# Seal.net
KiCad netlist of a schematic drawn in EAGLE
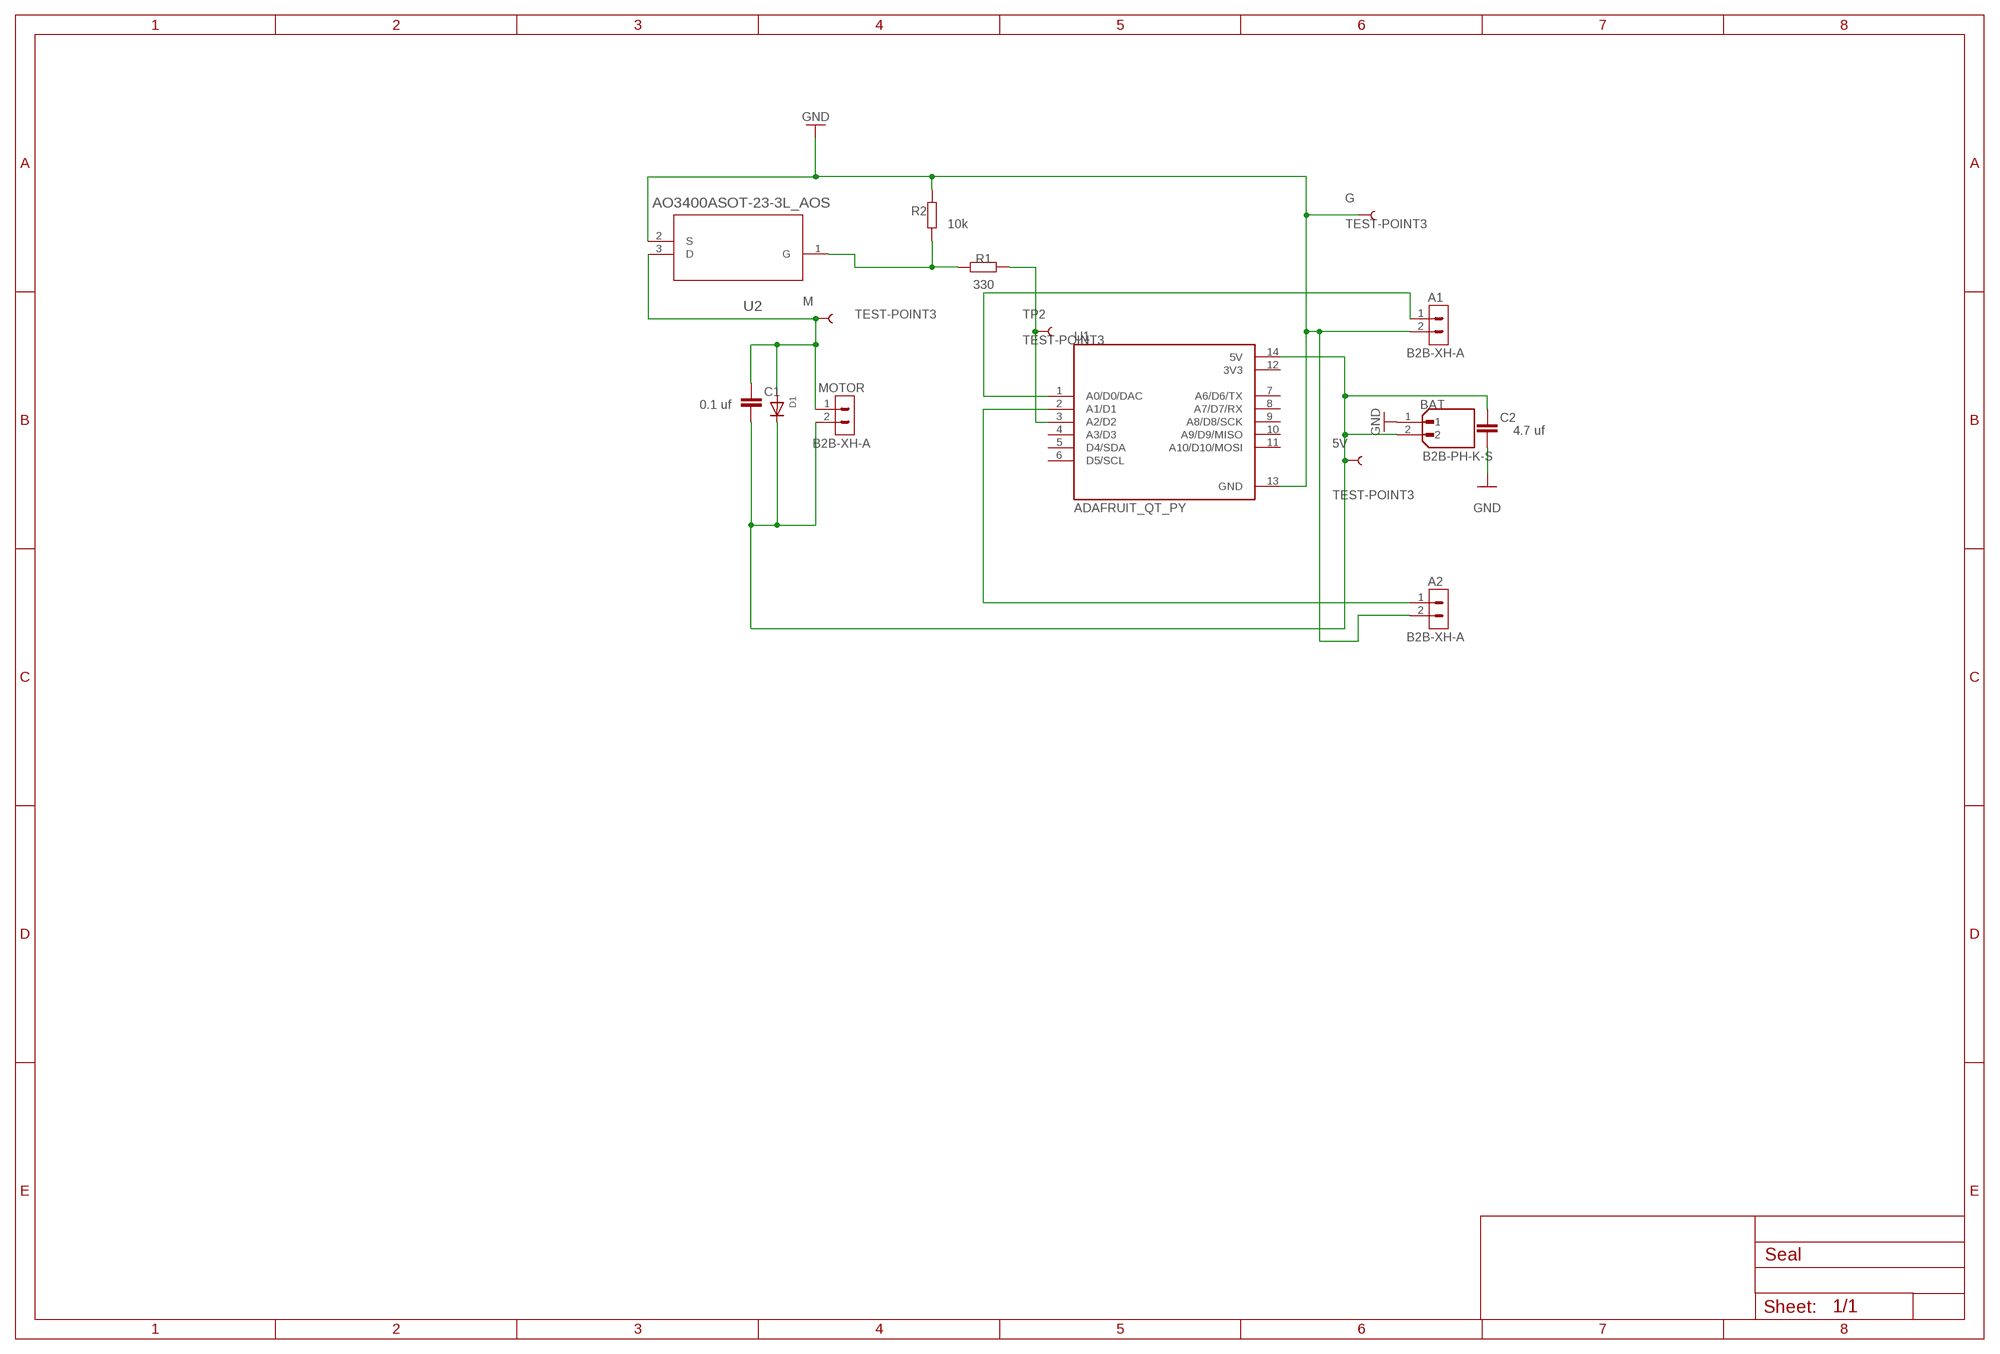
[diagram p0: schematic, sheet 1]

(export (version "E")
  (design (tool "Eeschema 10.0.6"))
  (components
    (comp (ref "5V")
      (value "TEST-POINT3")
      (footprint "eagle-import:PAD.03X.03")
      (libsource (lib "eagle-import") (part "TEST-POINT3"))
    )
    (comp (ref "A1")
      (value "B2B-XH-A")
      (footprint "eagle-import:B2B-XH-A")
      (fields (field (name "MANUFACTURER") "JST Sales America Inc."))
      (libsource (lib "eagle-import") (part "B2B-XH-A"))
    )
    (comp (ref "A2")
      (value "B2B-XH-A")
      (footprint "eagle-import:B2B-XH-A")
      (fields (field (name "MANUFACTURER") "JST Sales America Inc."))
      (libsource (lib "eagle-import") (part "B2B-XH-A"))
    )
    (comp (ref "BAT")
      (value "B2B-PH-K-S")
      (footprint "eagle-import:JST_B2B-PH-K-S")
      (fields (field (name "MF") "JST Sales"))
      (libsource (lib "eagle-import") (part "B2B-PH-K-S"))
    )
    (comp (ref "C1")
      (value "0.1 uf")
      (footprint "eagle-import:CAPC1608X85")
      (libsource (lib "eagle-import") (part "CCHIP-0603(1608-METRIC)_"))
    )
    (comp (ref "C2")
      (value "4.7 uf")
      (footprint "eagle-import:CAPC1608X85")
      (libsource (lib "eagle-import") (part "CCHIP-0603(1608-METRIC)_"))
    )
    (comp (ref "D1")
      (value "DIODESOD-123")
      (footprint "eagle-import:SOD-123")
      (libsource (lib "eagle-import") (part "DIODESOD-123"))
    )
    (comp (ref "G")
      (value "TEST-POINT3")
      (footprint "eagle-import:PAD.03X.03")
      (libsource (lib "eagle-import") (part "TEST-POINT3"))
    )
    (comp (ref "M")
      (value "TEST-POINT3")
      (footprint "eagle-import:PAD.03X.03")
      (libsource (lib "eagle-import") (part "TEST-POINT3"))
    )
    (comp (ref "MOTOR")
      (value "B2B-XH-A")
      (footprint "eagle-import:B2B-XH-A")
      (fields (field (name "MANUFACTURER") "JST Sales America Inc."))
      (libsource (lib "eagle-import") (part "B2B-XH-A"))
    )
    (comp (ref "R1")
      (value "330")
      (footprint "eagle-import:RESC1005X40")
      (libsource (lib "eagle-import") (part "RCHIP-0402(1005-METRIC)_"))
    )
    (comp (ref "R2")
      (value "10k")
      (footprint "eagle-import:RESC1005X40")
      (libsource (lib "eagle-import") (part "RCHIP-0402(1005-METRIC)_"))
    )
    (comp (ref "TP2")
      (value "TEST-POINT3")
      (footprint "eagle-import:PAD.03X.03")
      (libsource (lib "eagle-import") (part "TEST-POINT3"))
    )
    (comp (ref "U1")
      (value "ADAFRUIT_QT_PY")
      (footprint "eagle-import:MODULE_ADAFRUIT_QT_PY")
      (fields (field (name "MF") "Adafruit Industries") (field (name "MP") "Adafruit QT Py"))
      (libsource (lib "eagle-import") (part "ADAFRUIT_QT_PY"))
    )
    (comp (ref "U2")
      (value "AO3400ASOT-23-3L_AOS")
      (footprint "eagle-import:SOT-23-3L_AOS")
      (fields
        (field (name "MANUFACTURER_PART_NUMBER") "AO3400A")
        (field (name "COPYRIGHT") "Copyright (C) 2026 Ultra Librarian. All rights reserved.")
      )
      (libsource (lib "eagle-import") (part "AO3400ASOT-23-3L_AOS"))
    )
  )
  (nets
    (net (code "1") (name "/3V3") (class "Default")
      (node (ref "U1") (pin "12") (pinfunction "3V3_12") (pintype "power_in"))
    )
    (net (code "2") (name "GND") (class "Default")
      (node (ref "A1") (pin "2") (pinfunction "2_2") (pintype "passive"))
      (node (ref "A2") (pin "2") (pinfunction "2_2") (pintype "passive"))
      (node (ref "BAT") (pin "1") (pinfunction "1_1") (pintype "passive"))
      (node (ref "C2") (pin "2") (pinfunction "2_2") (pintype "passive"))
      (node (ref "G") (pin "1") (pinfunction "1_1") (pintype "bidirectional"))
      (node (ref "R2") (pin "2") (pinfunction "2_2") (pintype "passive"))
      (node (ref "U1") (pin "13") (pinfunction "GND_13") (pintype "power_in"))
      (node (ref "U2") (pin "2") (pinfunction "S_2") (pintype "passive"))
    )
    (net (code "3") (name "Net-(U1-5V)") (class "Default")
      (node (ref "5V") (pin "1") (pinfunction "1_1") (pintype "bidirectional"))
      (node (ref "BAT") (pin "2") (pinfunction "2_2") (pintype "passive"))
      (node (ref "C1") (pin "2") (pinfunction "2_2") (pintype "passive"))
      (node (ref "C2") (pin "1") (pinfunction "1_1") (pintype "passive"))
      (node (ref "D1") (pin "C") (pinfunction "C_C") (pintype "passive"))
      (node (ref "MOTOR") (pin "2") (pinfunction "2_2") (pintype "passive"))
      (node (ref "U1") (pin "14") (pinfunction "5V_14") (pintype "power_in"))
    )
    (net (code "4") (name "Net-(U1-A0{slash}D0{slash}DAC)") (class "Default")
      (node (ref "A1") (pin "1") (pinfunction "1_1") (pintype "passive"))
      (node (ref "U1") (pin "1") (pinfunction "A0/D0/DAC_1") (pintype "bidirectional"))
    )
    (net (code "5") (name "Net-(U1-A1{slash}D1)") (class "Default")
      (node (ref "A2") (pin "1") (pinfunction "1_1") (pintype "passive"))
      (node (ref "U1") (pin "2") (pinfunction "A1/D1_2") (pintype "bidirectional"))
    )
    (net (code "6") (name "Net-(U1-A2{slash}D2)") (class "Default")
      (node (ref "R1") (pin "2") (pinfunction "2_2") (pintype "passive"))
      (node (ref "TP2") (pin "1") (pinfunction "1_1") (pintype "bidirectional"))
      (node (ref "U1") (pin "3") (pinfunction "A2/D2_3") (pintype "bidirectional"))
    )
    (net (code "7") (name "Net-(U2-D)") (class "Default")
      (node (ref "C1") (pin "1") (pinfunction "1_1") (pintype "passive"))
      (node (ref "D1") (pin "A") (pinfunction "A_A") (pintype "passive"))
      (node (ref "M") (pin "1") (pinfunction "1_1") (pintype "bidirectional"))
      (node (ref "MOTOR") (pin "1") (pinfunction "1_1") (pintype "passive"))
      (node (ref "U2") (pin "3") (pinfunction "D_3") (pintype "passive"))
    )
    (net (code "8") (name "Net-(U2-G)") (class "Default")
      (node (ref "R1") (pin "1") (pinfunction "1_1") (pintype "passive"))
      (node (ref "R2") (pin "1") (pinfunction "1_1") (pintype "passive"))
      (node (ref "U2") (pin "1") (pinfunction "G_1") (pintype "passive"))
    )
    (net (code "9") (name "unconnected-(U1-A3{slash}D3-Pad4)") (class "Default")
      (node (ref "U1") (pin "4") (pinfunction "A3/D3_4") (pintype "bidirectional"))
    )
    (net (code "10") (name "unconnected-(U1-A6{slash}D6{slash}TX-Pad7)") (class "Default")
      (node (ref "U1") (pin "7") (pinfunction "A6/D6/TX_7") (pintype "bidirectional"))
    )
    (net (code "11") (name "unconnected-(U1-A7{slash}D7{slash}RX-Pad8)") (class "Default")
      (node (ref "U1") (pin "8") (pinfunction "A7/D7/RX_8") (pintype "bidirectional"))
    )
    (net (code "12") (name "unconnected-(U1-A8{slash}D8{slash}SCK-Pad9)") (class "Default")
      (node (ref "U1") (pin "9") (pinfunction "A8/D8/SCK_9") (pintype "bidirectional"))
    )
    (net (code "13") (name "unconnected-(U1-A9{slash}D9{slash}MISO-Pad10)") (class "Default")
      (node (ref "U1") (pin "10") (pinfunction "A9/D9/MISO_10") (pintype "bidirectional"))
    )
    (net (code "14") (name "unconnected-(U1-A10{slash}D10{slash}MOSI-Pad11)") (class "Default")
      (node (ref "U1") (pin "11") (pinfunction "A10/D10/MOSI_11") (pintype "bidirectional"))
    )
    (net (code "15") (name "unconnected-(U1-D4{slash}SDA-Pad5)") (class "Default")
      (node (ref "U1") (pin "5") (pinfunction "D4/SDA_5") (pintype "bidirectional"))
    )
    (net (code "16") (name "unconnected-(U1-D5{slash}SCL-Pad6)") (class "Default")
      (node (ref "U1") (pin "6") (pinfunction "D5/SCL_6") (pintype "bidirectional"))
    )
  )
)
